# Nu_Preamp.net
KiCad netlist of a schematic drawn in EAGLE
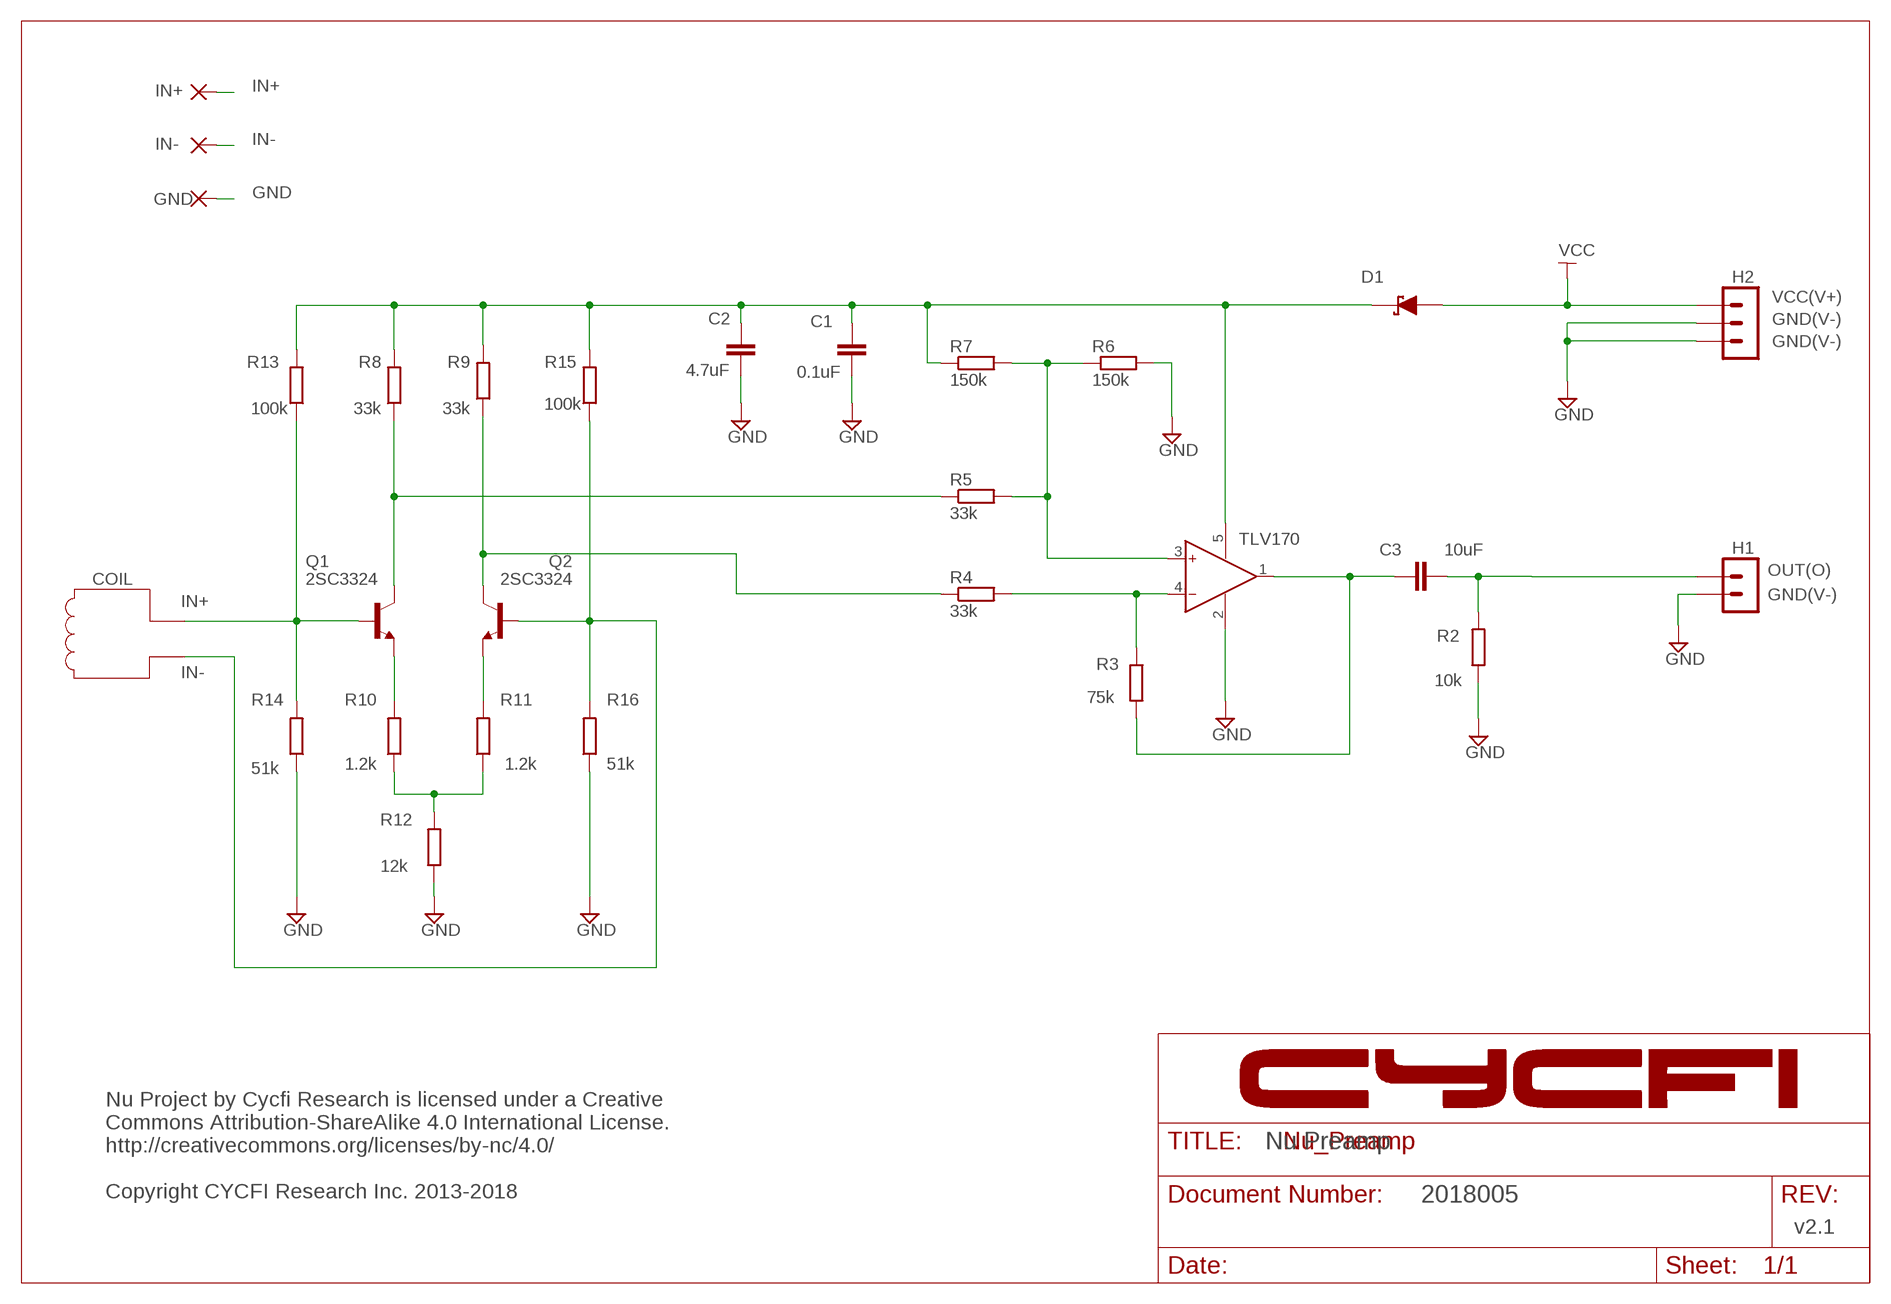
[diagram p0: schematic, sheet 1]

(export (version "E")
  (design (tool "Eeschema 10.0.6"))
  (components
    (comp (ref "C1")
      (value "0.1uF")
      (footprint "eagle-import:C0402")
      (libsource (lib "eagle-import") (part "C-EUC0402"))
    )
    (comp (ref "C2")
      (value "4.7uF")
      (footprint "eagle-import:C0603_NK")
      (libsource (lib "eagle-import") (part "C0603_NK"))
    )
    (comp (ref "C3")
      (value "10uF")
      (footprint "eagle-import:C0603_NK")
      (libsource (lib "eagle-import") (part "C0603_NK"))
    )
    (comp (ref "D1")
      (value "D_SCHOTTKYL")
      (footprint "eagle-import:SOD-323")
      (libsource (lib "eagle-import") (part "D_SCHOTTKYL"))
    )
    (comp (ref "GND")
      (value "SMD2")
      (footprint "eagle-import:SMD1,27-2,54")
      (libsource (lib "eagle-import") (part "SMD2"))
    )
    (comp (ref "H1")
      (value "2P-2MM-TH-MALE")
      (footprint "eagle-import:2P-2MM-TH")
      (libsource (lib "eagle-import") (part "2P-2MM-TH-MALE"))
    )
    (comp (ref "H2")
      (value "3P-2MM-TH-MALE")
      (footprint "eagle-import:3P-2MM-TH")
      (libsource (lib "eagle-import") (part "3P-2MM-TH-MALE"))
    )
    (comp (ref "IN+")
      (value "SMD2")
      (footprint "eagle-import:SMD1,27-2,54")
      (libsource (lib "eagle-import") (part "SMD2"))
    )
    (comp (ref "IN-")
      (value "SMD2")
      (footprint "eagle-import:SMD1,27-2,54")
      (libsource (lib "eagle-import") (part "SMD2"))
    )
    (comp (ref "Q1")
      (value "2SC3324")
      (footprint "eagle-import:SOT23")
      (libsource (lib "eagle-import") (part "2SC3324"))
    )
    (comp (ref "Q2")
      (value "2SC3324")
      (footprint "eagle-import:SOT23")
      (libsource (lib "eagle-import") (part "2SC3324"))
    )
    (comp (ref "R2")
      (value "10k")
      (footprint "eagle-import:R0402")
      (libsource (lib "eagle-import") (part "R-EU_R0402"))
    )
    (comp (ref "R3")
      (value "75k")
      (footprint "eagle-import:R0402")
      (libsource (lib "eagle-import") (part "resistor_R-EU_R0402"))
    )
    (comp (ref "R4")
      (value "33k")
      (footprint "eagle-import:R0402")
      (libsource (lib "eagle-import") (part "resistor_R-EU_R0402"))
    )
    (comp (ref "R5")
      (value "33k")
      (footprint "eagle-import:R0402")
      (libsource (lib "eagle-import") (part "resistor_R-EU_R0402"))
    )
    (comp (ref "R6")
      (value "150k")
      (footprint "eagle-import:R0402")
      (libsource (lib "eagle-import") (part "resistor_R-EU_R0402"))
    )
    (comp (ref "R7")
      (value "150k")
      (footprint "eagle-import:R0402")
      (libsource (lib "eagle-import") (part "resistor_R-EU_R0402"))
    )
    (comp (ref "R8")
      (value "33k")
      (footprint "eagle-import:R0402")
      (libsource (lib "eagle-import") (part "R-EU_R0402"))
    )
    (comp (ref "R9")
      (value "33k")
      (footprint "eagle-import:R0402")
      (libsource (lib "eagle-import") (part "R-EU_R0402"))
    )
    (comp (ref "R10")
      (value "1.2k")
      (footprint "eagle-import:R0402")
      (libsource (lib "eagle-import") (part "R-EU_R0402"))
    )
    (comp (ref "R11")
      (value "1.2k")
      (footprint "eagle-import:R0402")
      (libsource (lib "eagle-import") (part "R-EU_R0402"))
    )
    (comp (ref "R12")
      (value "12k")
      (footprint "eagle-import:R0402")
      (libsource (lib "eagle-import") (part "R-EU_R0402"))
    )
    (comp (ref "R13")
      (value "100k")
      (footprint "eagle-import:R0402")
      (libsource (lib "eagle-import") (part "R-EU_R0402"))
    )
    (comp (ref "R14")
      (value "51k")
      (footprint "eagle-import:R0402")
      (libsource (lib "eagle-import") (part "R-EU_R0402"))
    )
    (comp (ref "R15")
      (value "100k")
      (footprint "eagle-import:R0402")
      (libsource (lib "eagle-import") (part "R-EU_R0402"))
    )
    (comp (ref "R16")
      (value "51k")
      (footprint "eagle-import:R0402")
      (libsource (lib "eagle-import") (part "R-EU_R0402"))
    )
    (comp (ref "U1")
      (value "TLV170")
      (footprint "eagle-import:SOT23-5")
      (libsource (lib "eagle-import") (part "TLV170"))
    )
  )
  (nets
    (net (code "1") (name "/IN+") (class "Default")
      (node (ref "IN+") (pin "1") (pinfunction "P_1") (pintype "passive"))
      (node (ref "Q1") (pin "1") (pinfunction "B_1") (pintype "passive"))
      (node (ref "R13") (pin "1") (pinfunction "1_1") (pintype "passive"))
      (node (ref "R14") (pin "2") (pinfunction "2_2") (pintype "passive"))
    )
    (net (code "2") (name "/IN-") (class "Default")
      (node (ref "IN-") (pin "1") (pinfunction "P_1") (pintype "passive"))
      (node (ref "Q2") (pin "1") (pinfunction "B_1") (pintype "passive"))
      (node (ref "R15") (pin "1") (pinfunction "1_1") (pintype "passive"))
      (node (ref "R16") (pin "2") (pinfunction "2_2") (pintype "passive"))
    )
    (net (code "3") (name "GND") (class "Default")
      (node (ref "C1") (pin "2") (pinfunction "2_2") (pintype "passive"))
      (node (ref "C2") (pin "1") (pinfunction "1_1") (pintype "passive"))
      (node (ref "GND") (pin "1") (pinfunction "P_1") (pintype "passive"))
      (node (ref "H1") (pin "P$2") (pinfunction "2_P$2") (pintype "passive"))
      (node (ref "H2") (pin "P$2") (pinfunction "2_P$2") (pintype "passive"))
      (node (ref "H2") (pin "P$3") (pinfunction "3_P$3") (pintype "passive"))
      (node (ref "R12") (pin "1") (pinfunction "1_1") (pintype "passive"))
      (node (ref "R14") (pin "1") (pinfunction "1_1") (pintype "passive"))
      (node (ref "R16") (pin "1") (pinfunction "1_1") (pintype "passive"))
      (node (ref "R2") (pin "1") (pinfunction "1_1") (pintype "passive"))
      (node (ref "R6") (pin "2") (pinfunction "2_2") (pintype "passive"))
      (node (ref "U1") (pin "2") (pinfunction "V-_2") (pintype "power_in"))
    )
    (net (code "4") (name "Net-(D1-A)") (class "Default")
      (node (ref "D1") (pin "1") (pinfunction "A_1") (pintype "passive"))
      (node (ref "H2") (pin "P$1") (pinfunction "1_P$1") (pintype "passive"))
    )
    (net (code "5") (name "Net-(D1-C)") (class "Default")
      (node (ref "C1") (pin "1") (pinfunction "1_1") (pintype "passive"))
      (node (ref "C2") (pin "2") (pinfunction "2_2") (pintype "passive"))
      (node (ref "D1") (pin "2") (pinfunction "C_2") (pintype "passive"))
      (node (ref "R13") (pin "2") (pinfunction "2_2") (pintype "passive"))
      (node (ref "R15") (pin "2") (pinfunction "2_2") (pintype "passive"))
      (node (ref "R7") (pin "1") (pinfunction "1_1") (pintype "passive"))
      (node (ref "R8") (pin "2") (pinfunction "2_2") (pintype "passive"))
      (node (ref "R9") (pin "2") (pinfunction "2_2") (pintype "passive"))
      (node (ref "U1") (pin "5") (pinfunction "V+_5") (pintype "power_in"))
    )
    (net (code "6") (name "Net-(H1-1)") (class "Default")
      (node (ref "C3") (pin "2") (pinfunction "2_2") (pintype "passive"))
      (node (ref "H1") (pin "P$1") (pinfunction "1_P$1") (pintype "passive"))
      (node (ref "R2") (pin "2") (pinfunction "2_2") (pintype "passive"))
    )
    (net (code "7") (name "Net-(Q1-C)") (class "Default")
      (node (ref "Q1") (pin "3") (pinfunction "C_3") (pintype "passive"))
      (node (ref "R5") (pin "1") (pinfunction "1_1") (pintype "passive"))
      (node (ref "R8") (pin "1") (pinfunction "1_1") (pintype "passive"))
    )
    (net (code "8") (name "Net-(Q1-E)") (class "Default")
      (node (ref "Q1") (pin "2") (pinfunction "E_2") (pintype "passive"))
      (node (ref "R10") (pin "2") (pinfunction "2_2") (pintype "passive"))
    )
    (net (code "9") (name "Net-(Q2-C)") (class "Default")
      (node (ref "Q2") (pin "3") (pinfunction "C_3") (pintype "passive"))
      (node (ref "R4") (pin "1") (pinfunction "1_1") (pintype "passive"))
      (node (ref "R9") (pin "1") (pinfunction "1_1") (pintype "passive"))
    )
    (net (code "10") (name "Net-(Q2-E)") (class "Default")
      (node (ref "Q2") (pin "2") (pinfunction "E_2") (pintype "passive"))
      (node (ref "R11") (pin "2") (pinfunction "2_2") (pintype "passive"))
    )
    (net (code "11") (name "Net-(R10-Pad1)") (class "Default")
      (node (ref "R10") (pin "1") (pinfunction "1_1") (pintype "passive"))
      (node (ref "R11") (pin "1") (pinfunction "1_1") (pintype "passive"))
      (node (ref "R12") (pin "2") (pinfunction "2_2") (pintype "passive"))
    )
    (net (code "12") (name "Net-(U1A-IN+)") (class "Default")
      (node (ref "R5") (pin "2") (pinfunction "2_2") (pintype "passive"))
      (node (ref "R6") (pin "1") (pinfunction "1_1") (pintype "passive"))
      (node (ref "R7") (pin "2") (pinfunction "2_2") (pintype "passive"))
      (node (ref "U1") (pin "3") (pinfunction "IN+_3") (pintype "input"))
    )
    (net (code "13") (name "Net-(U1A-IN-)") (class "Default")
      (node (ref "R3") (pin "2") (pinfunction "2_2") (pintype "passive"))
      (node (ref "R4") (pin "2") (pinfunction "2_2") (pintype "passive"))
      (node (ref "U1") (pin "4") (pinfunction "IN-_4") (pintype "input"))
    )
    (net (code "14") (name "Net-(U1A-OUT)") (class "Default")
      (node (ref "C3") (pin "1") (pinfunction "1_1") (pintype "passive"))
      (node (ref "R3") (pin "1") (pinfunction "1_1") (pintype "passive"))
      (node (ref "U1") (pin "1") (pinfunction "OUT_1") (pintype "output"))
    )
  )
)
